# 06_LMS7002M_RF2.net
KiCad netlist of a schematic drawn in Altium Designer
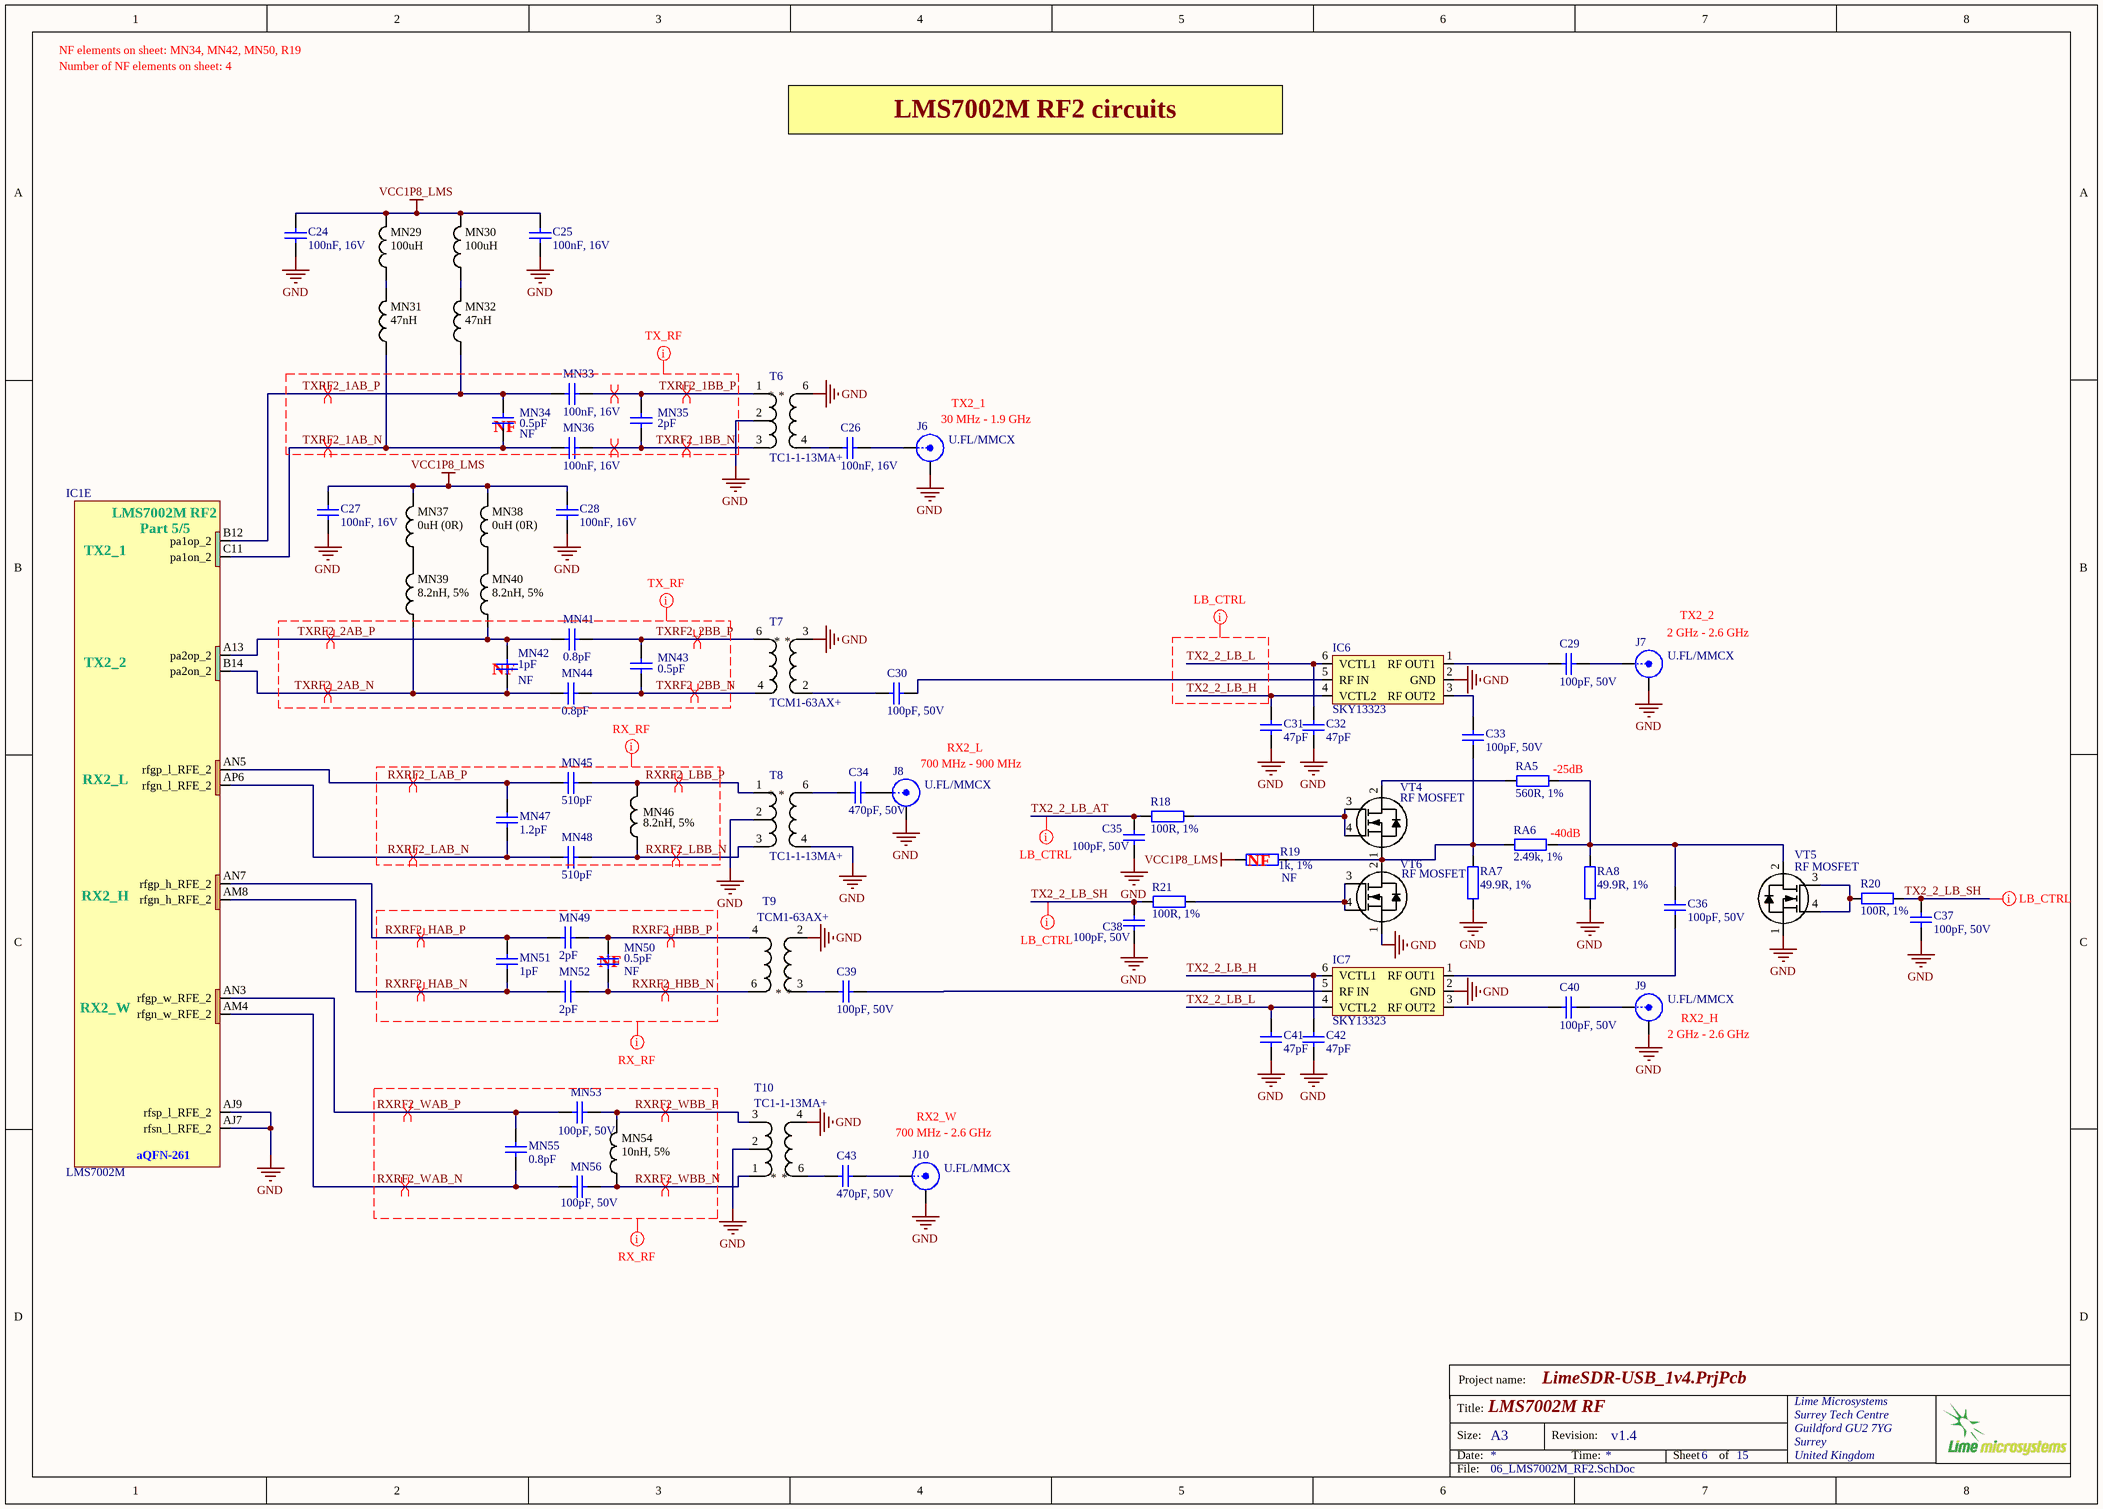
[diagram p0: 06_LMS7002M_RF2.SchDoc]

(export (version "E")
  (design (tool "Eeschema 10.0.6"))
  (components
    (comp (ref "C24")
      (value "100nF, 16V")
      (footprint "CAP0402")
      (fields
        (field (name "MANUFACTURER") "Murata Electronics")
        (field (name "TOLERANCE") "10 %")
        (field (name "MANUFACTURER PART NUMBER") "GRM155R71C104KA88D")
      )
      (libsource (lib "LimeMicroAltiumLib_schLib") (part "Cap_0402"))
    )
    (comp (ref "C25")
      (value "100nF, 16V")
      (footprint "CAP0402")
      (fields
        (field (name "MANUFACTURER") "Murata Electronics")
        (field (name "TOLERANCE") "10 %")
        (field (name "MANUFACTURER PART NUMBER") "GRM155R71C104KA88D")
      )
      (libsource (lib "LimeMicroAltiumLib_schLib") (part "Cap_0402"))
    )
    (comp (ref "C26")
      (value "100nF, 16V")
      (footprint "CAP0402")
      (fields
        (field (name "MANUFACTURER") "Murata Electronics")
        (field (name "TOLERANCE") "10 %")
        (field (name "MANUFACTURER PART NUMBER") "GRM155R71C104KA88D")
      )
      (libsource (lib "LimeMicroAltiumLib_schLib") (part "Cap_0402"))
    )
    (comp (ref "C27")
      (value "100nF, 16V")
      (footprint "CAP0402")
      (fields
        (field (name "MANUFACTURER") "Murata Electronics")
        (field (name "TOLERANCE") "10 %")
        (field (name "MANUFACTURER PART NUMBER") "GRM155R71C104KA88D")
      )
      (libsource (lib "LimeMicroAltiumLib_schLib") (part "Cap_0402"))
    )
    (comp (ref "C28")
      (value "100nF, 16V")
      (footprint "CAP0402")
      (fields
        (field (name "MANUFACTURER") "Murata Electronics")
        (field (name "TOLERANCE") "10 %")
        (field (name "MANUFACTURER PART NUMBER") "GRM155R71C104KA88D")
      )
      (libsource (lib "LimeMicroAltiumLib_schLib") (part "Cap_0402"))
    )
    (comp (ref "C29")
      (value "100pF, 50V")
      (footprint "CAP0402")
      (fields (field (name "TOLERANCE") "±5%") (field (name "MANUFACTURER") "Yageo"))
      (libsource (lib "LimeMicroAltiumLib_schLib") (part "Cap_0402"))
    )
    (comp (ref "C30")
      (value "100pF, 50V")
      (footprint "CAP0402")
      (fields (field (name "TOLERANCE") "±5%") (field (name "MANUFACTURER") "Yageo"))
      (libsource (lib "LimeMicroAltiumLib_schLib") (part "Cap_0402"))
    )
    (comp (ref "C31")
      (value "47pF")
      (footprint "CAP0402")
      (fields (field (name "TOLERANCE") "±1%") (field (name "MANUFACTURER") "TDK Corporation"))
      (libsource (lib "LimeMicroAltiumLib_schLib") (part "Cap_0402"))
    )
    (comp (ref "C32")
      (value "47pF")
      (footprint "CAP0402")
      (fields (field (name "TOLERANCE") "±1%") (field (name "MANUFACTURER") "TDK Corporation"))
      (libsource (lib "LimeMicroAltiumLib_schLib") (part "Cap_0402"))
    )
    (comp (ref "C33")
      (value "100pF, 50V")
      (footprint "CAP0402")
      (fields (field (name "TOLERANCE") "±5%") (field (name "MANUFACTURER") "Yageo"))
      (libsource (lib "LimeMicroAltiumLib_schLib") (part "Cap_0402"))
    )
    (comp (ref "C34")
      (value "470pF, 50V")
      (footprint "CAP0402")
      (fields
        (field (name "MANUFACTURER PART NUMBER") "C1005C0G1H471J050BA")
        (field (name "TOLERANCE") "±5%")
        (field (name "MANUFACTURER") "TDK Corporation")
      )
      (libsource (lib "LimeMicroAltiumLib_schLib") (part "Cap_0402"))
    )
    (comp (ref "C35")
      (value "100pF, 50V")
      (footprint "CAP0402")
      (fields (field (name "TOLERANCE") "±5%") (field (name "MANUFACTURER") "Yageo"))
      (libsource (lib "LimeMicroAltiumLib_schLib") (part "Cap_0402"))
    )
    (comp (ref "C36")
      (value "100pF, 50V")
      (footprint "CAP0402")
      (fields (field (name "TOLERANCE") "±5%") (field (name "MANUFACTURER") "Yageo"))
      (libsource (lib "LimeMicroAltiumLib_schLib") (part "Cap_0402"))
    )
    (comp (ref "C37")
      (value "100pF, 50V")
      (footprint "CAP0402")
      (fields (field (name "TOLERANCE") "±5%") (field (name "MANUFACTURER") "Yageo"))
      (libsource (lib "LimeMicroAltiumLib_schLib") (part "Cap_0402"))
    )
    (comp (ref "C38")
      (value "100pF, 50V")
      (footprint "CAP0402")
      (fields (field (name "TOLERANCE") "±5%") (field (name "MANUFACTURER") "Yageo"))
      (libsource (lib "LimeMicroAltiumLib_schLib") (part "Cap_0402"))
    )
    (comp (ref "C39")
      (value "100pF, 50V")
      (footprint "CAP0402")
      (fields (field (name "TOLERANCE") "±5%") (field (name "MANUFACTURER") "Yageo"))
      (libsource (lib "LimeMicroAltiumLib_schLib") (part "Cap_0402"))
    )
    (comp (ref "C40")
      (value "100pF, 50V")
      (footprint "CAP0402")
      (fields (field (name "TOLERANCE") "±5%") (field (name "MANUFACTURER") "Yageo"))
      (libsource (lib "LimeMicroAltiumLib_schLib") (part "Cap_0402"))
    )
    (comp (ref "C41")
      (value "47pF")
      (footprint "CAP0402")
      (fields (field (name "TOLERANCE") "±1%") (field (name "MANUFACTURER") "TDK Corporation"))
      (libsource (lib "LimeMicroAltiumLib_schLib") (part "Cap_0402"))
    )
    (comp (ref "C42")
      (value "47pF")
      (footprint "CAP0402")
      (fields (field (name "TOLERANCE") "±1%") (field (name "MANUFACTURER") "TDK Corporation"))
      (libsource (lib "LimeMicroAltiumLib_schLib") (part "Cap_0402"))
    )
    (comp (ref "C43")
      (value "470pF, 50V")
      (footprint "CAP0402")
      (fields
        (field (name "MANUFACTURER PART NUMBER") "C1005C0G1H471J050BA")
        (field (name "TOLERANCE") "±5%")
        (field (name "MANUFACTURER") "TDK Corporation")
      )
      (libsource (lib "LimeMicroAltiumLib_schLib") (part "Cap_0402"))
    )
    (comp (ref "IC1")
      (value "LMS7002M")
      (footprint "LMS7002M_v3")
      (fields (field (name "MANUFACTURER") "Lime Microsystems"))
      (libsource (lib "LimeMicroAltiumLib_schLib") (part "LMS7002M"))
    )
    (comp (ref "IC6")
      (value "SKY13323")
      (footprint "SKY13323-378LF")
      (description "SKY13323-378LF: 0.1-3.0 GHz GaAs SPDT Switch")
      (fields (field (name "MANUFACTURER") "Skyworks Solutions Inc."))
      (libsource (lib "LimeMicroAltiumLib_schLib") (part "SKY13323"))
    )
    (comp (ref "IC7")
      (value "SKY13323")
      (footprint "SKY13323-378LF")
      (description "SKY13323-378LF: 0.1-3.0 GHz GaAs SPDT Switch")
      (fields (field (name "MANUFACTURER") "Skyworks Solutions Inc."))
      (libsource (lib "LimeMicroAltiumLib_schLib") (part "SKY13323"))
    )
    (comp (ref "J6")
      (value "U.FL/MMCX")
      (footprint "MMCX_UFL_conn_u")
      (description "CONN UMC RCPT STR 50 OHM SMD")
      (fields (field (name "MANUFACTURER") "Molex, LLC"))
      (libsource (lib "LimeMicroAltiumLib_schLib") (part "RF_IF_connector"))
    )
    (comp (ref "J7")
      (value "U.FL/MMCX")
      (footprint "MMCX_UFL_conn_u")
      (description "CONN UMC RCPT STR 50 OHM SMD")
      (fields (field (name "MANUFACTURER") "Molex, LLC"))
      (libsource (lib "LimeMicroAltiumLib_schLib") (part "RF_IF_connector"))
    )
    (comp (ref "J8")
      (value "U.FL/MMCX")
      (footprint "MMCX_UFL_conn_u")
      (description "CONN UMC RCPT STR 50 OHM SMD")
      (fields (field (name "MANUFACTURER") "Molex, LLC"))
      (libsource (lib "LimeMicroAltiumLib_schLib") (part "RF_IF_connector"))
    )
    (comp (ref "J9")
      (value "U.FL/MMCX")
      (footprint "MMCX_UFL_conn_u")
      (description "CONN UMC RCPT STR 50 OHM SMD")
      (fields (field (name "MANUFACTURER") "Molex, LLC"))
      (libsource (lib "LimeMicroAltiumLib_schLib") (part "RF_IF_connector"))
    )
    (comp (ref "J10")
      (value "U.FL/MMCX")
      (footprint "MMCX_UFL_conn_u")
      (description "CONN UMC RCPT STR 50 OHM SMD")
      (fields (field (name "MANUFACTURER") "Molex, LLC"))
      (libsource (lib "LimeMicroAltiumLib_schLib") (part "RF_IF_connector"))
    )
    (comp (ref "MN29")
      (value "100uH")
      (footprint "RES0805")
      (fields
        (field (name "TOLERANCE") "±10%")
        (field (name "MANUFACTURER") "TDK Corporation")
        (field (name "MANUFACTURER PART NUMBER") "MLF2012C101KT000")
      )
      (libsource (lib "LimeMicroAltiumLib_schLib") (part "Inductor_0603"))
    )
    (comp (ref "MN30")
      (value "100uH")
      (footprint "RES0805")
      (fields
        (field (name "TOLERANCE") "±10%")
        (field (name "MANUFACTURER") "TDK Corporation")
        (field (name "MANUFACTURER PART NUMBER") "MLF2012C101KT000")
      )
      (libsource (lib "LimeMicroAltiumLib_schLib") (part "Inductor_0603"))
    )
    (comp (ref "MN31")
      (value "47nH")
      (footprint "RES0402")
      (fields
        (field (name "MANUFACTURER") "COILCRAFT")
        (field (name "MANUFACTURER PART NUMBER") "0402HP-47NXJLU")
      )
      (libsource (lib "LimeMicroAltiumLib_schLib") (part "Inductor_0603"))
    )
    (comp (ref "MN32")
      (value "47nH")
      (footprint "RES0402")
      (fields
        (field (name "MANUFACTURER") "COILCRAFT")
        (field (name "MANUFACTURER PART NUMBER") "0402HP-47NXJLU")
      )
      (libsource (lib "LimeMicroAltiumLib_schLib") (part "Inductor_0603"))
    )
    (comp (ref "MN33")
      (value "100nF, 16V")
      (footprint "CAP0402")
      (fields
        (field (name "MANUFACTURER") "Murata Electronics")
        (field (name "TOLERANCE") "10 %")
        (field (name "MANUFACTURER PART NUMBER") "GRM155R71C104KA88D")
      )
      (libsource (lib "LimeMicroAltiumLib_schLib") (part "Cap_0402"))
    )
    (comp (ref "MN34")
      (value "0.5pF")
      (footprint "CAP0402")
      (fields
        (field (name "ASSEMBLY INFO") "NF")
        (field (name "TOLERANCE") "±0.25pF")
        (field (name "MANUFACTURER") "Yageo")
      )
      (libsource (lib "LimeMicroAltiumLib_schLib") (part "Cap_0402"))
    )
    (comp (ref "MN35")
      (value "2pF")
      (footprint "CAP0402")
      (fields (field (name "MANUFACTURER PART NUMBER") "04025U2R0BAT2A") (field (name "MANUFACTURER") "AVX"))
      (libsource (lib "LimeMicroAltiumLib_schLib") (part "Cap_0402"))
    )
    (comp (ref "MN36")
      (value "100nF, 16V")
      (footprint "CAP0402")
      (fields
        (field (name "MANUFACTURER") "Murata Electronics")
        (field (name "TOLERANCE") "10 %")
        (field (name "MANUFACTURER PART NUMBER") "GRM155R71C104KA88D")
      )
      (libsource (lib "LimeMicroAltiumLib_schLib") (part "Cap_0402"))
    )
    (comp (ref "MN37")
      (value "0uH (0R)")
      (footprint "RES0805")
      (fields (field (name "MANUFACTURER") "BOURNS"))
      (libsource (lib "LimeMicroAltiumLib_schLib") (part "Inductor_0603"))
    )
    (comp (ref "MN38")
      (value "0uH (0R)")
      (footprint "RES0805")
      (fields (field (name "MANUFACTURER") "BOURNS"))
      (libsource (lib "LimeMicroAltiumLib_schLib") (part "Inductor_0603"))
    )
    (comp (ref "MN39")
      (value "8.2nH, 5%")
      (footprint "RES0402")
      (fields (field (name "MANUFACTURER") "COILCRAFT"))
      (libsource (lib "LimeMicroAltiumLib_schLib") (part "Inductor_0603"))
    )
    (comp (ref "MN40")
      (value "8.2nH, 5%")
      (footprint "RES0402")
      (fields (field (name "MANUFACTURER") "COILCRAFT"))
      (libsource (lib "LimeMicroAltiumLib_schLib") (part "Inductor_0603"))
    )
    (comp (ref "MN41")
      (value "0.8pF")
      (footprint "CAP0402")
      (fields
        (field (name "TOLERANCE") "±0.1pF")
        (field (name "MANUFACTURER") "Murata Electronics North America")
        (field (name "MANUFACTURER PART NUMBER") "GRM1555C1HR80BA01D")
      )
      (libsource (lib "LimeMicroAltiumLib_schLib") (part "Cap_0402"))
    )
    (comp (ref "MN42")
      (value "1pF")
      (footprint "CAP0402")
      (fields
        (field (name "ASSEMBLY INFO") "NF")
        (field (name "MANUFACTURER") "TDK Corporation")
        (field (name "TOLERANCE") "±0.1pF")
      )
      (libsource (lib "LimeMicroAltiumLib_schLib") (part "Cap_0402"))
    )
    (comp (ref "MN43")
      (value "0.5pF")
      (footprint "CAP0402")
      (fields (field (name "TOLERANCE") "±0.25pF") (field (name "MANUFACTURER") "Yageo"))
      (libsource (lib "LimeMicroAltiumLib_schLib") (part "Cap_0402"))
    )
    (comp (ref "MN44")
      (value "0.8pF")
      (footprint "CAP0402")
      (fields
        (field (name "TOLERANCE") "±0.1pF")
        (field (name "MANUFACTURER") "Murata Electronics North America")
        (field (name "MANUFACTURER PART NUMBER") "GRM1555C1HR80BA01D")
      )
      (libsource (lib "LimeMicroAltiumLib_schLib") (part "Cap_0402"))
    )
    (comp (ref "MN45")
      (value "510pF")
      (footprint "CAP0402")
      (fields
        (field (name "TOLERANCE") "±5%")
        (field (name "MANUFACTURER") "Murata Electronics North America")
        (field (name "MANUFACTURER PART NUMBER") "GRM1555C1H511JA01D")
      )
      (libsource (lib "LimeMicroAltiumLib_schLib") (part "Cap_0402"))
    )
    (comp (ref "MN46")
      (value "8.2nH, 5%")
      (footprint "RES0402")
      (fields (field (name "MANUFACTURER") "COILCRAFT"))
      (libsource (lib "LimeMicroAltiumLib_schLib") (part "Inductor_0603"))
    )
    (comp (ref "MN47")
      (value "1.2pF")
      (footprint "CAP0402")
      (fields
        (field (name "MANUFACTURER") "Murata Electronics North America")
        (field (name "MANUFACTURER PART NUMBER") "GRM1555C1H1R2CA01D")
        (field (name "TOLERANCE") "±0.25pF")
      )
      (libsource (lib "LimeMicroAltiumLib_schLib") (part "Cap_0402"))
    )
    (comp (ref "MN48")
      (value "510pF")
      (footprint "CAP0402")
      (fields
        (field (name "TOLERANCE") "±5%")
        (field (name "MANUFACTURER") "Murata Electronics North America")
        (field (name "MANUFACTURER PART NUMBER") "GRM1555C1H511JA01D")
      )
      (libsource (lib "LimeMicroAltiumLib_schLib") (part "Cap_0402"))
    )
    (comp (ref "MN49")
      (value "2pF")
      (footprint "CAP0402")
      (fields (field (name "MANUFACTURER PART NUMBER") "04025U2R0BAT2A") (field (name "MANUFACTURER") "AVX"))
      (libsource (lib "LimeMicroAltiumLib_schLib") (part "Cap_0402"))
    )
    (comp (ref "MN50")
      (value "0.5pF")
      (footprint "CAP0402")
      (fields
        (field (name "ASSEMBLY INFO") "NF")
        (field (name "TOLERANCE") "±0.25pF")
        (field (name "MANUFACTURER") "Yageo")
      )
      (libsource (lib "LimeMicroAltiumLib_schLib") (part "Cap_0402"))
    )
    (comp (ref "MN51")
      (value "1pF")
      (footprint "CAP0402")
      (fields (field (name "MANUFACTURER") "TDK Corporation") (field (name "TOLERANCE") "±0.1pF"))
      (libsource (lib "LimeMicroAltiumLib_schLib") (part "Cap_0402"))
    )
    (comp (ref "MN52")
      (value "2pF")
      (footprint "CAP0402")
      (fields (field (name "MANUFACTURER PART NUMBER") "04025U2R0BAT2A") (field (name "MANUFACTURER") "AVX"))
      (libsource (lib "LimeMicroAltiumLib_schLib") (part "Cap_0402"))
    )
    (comp (ref "MN53")
      (value "100pF, 50V")
      (footprint "CAP0402")
      (fields (field (name "TOLERANCE") "±5%") (field (name "MANUFACTURER") "Yageo"))
      (libsource (lib "LimeMicroAltiumLib_schLib") (part "Cap_0402"))
    )
    (comp (ref "MN54")
      (value "10nH, 5%")
      (footprint "RES0402")
      (fields (field (name "MANUFACTURER") "COILCRAFT"))
      (libsource (lib "LimeMicroAltiumLib_schLib") (part "Inductor_0603"))
    )
    (comp (ref "MN55")
      (value "0.8pF")
      (footprint "CAP0402")
      (fields
        (field (name "TOLERANCE") "±0.1pF")
        (field (name "MANUFACTURER") "Murata Electronics North America")
        (field (name "MANUFACTURER PART NUMBER") "GRM1555C1HR80BA01D")
      )
      (libsource (lib "LimeMicroAltiumLib_schLib") (part "Cap_0402"))
    )
    (comp (ref "MN56")
      (value "100pF, 50V")
      (footprint "CAP0402")
      (fields (field (name "TOLERANCE") "±5%") (field (name "MANUFACTURER") "Yageo"))
      (libsource (lib "LimeMicroAltiumLib_schLib") (part "Cap_0402"))
    )
    (comp (ref "R18")
      (value "100R, 1%")
      (footprint "RES0402")
      (fields (field (name "TOLERANCE") "±1%") (field (name "MANUFACTURER") "Stackpole Electronics Inc."))
      (libsource (lib "LimeFPGAboard_schLib") (part "Res_0402"))
    )
    (comp (ref "R19")
      (value "1k, 1%")
      (footprint "RES0402")
      (fields
        (field (name "ASSEMBLY INFO") "NF")
        (field (name "MANUFACTURER") "Stackpole Electronics Inc")
        (field (name "TOLERANCE") "±1%")
      )
      (libsource (lib "LimeMicroAltiumLib_schLib") (part "Res_0402"))
    )
    (comp (ref "R20")
      (value "100R, 1%")
      (footprint "RES0402")
      (fields (field (name "TOLERANCE") "±1%") (field (name "MANUFACTURER") "Stackpole Electronics Inc."))
      (libsource (lib "LimeFPGAboard_schLib") (part "Res_0402"))
    )
    (comp (ref "R21")
      (value "100R, 1%")
      (footprint "RES0402")
      (fields (field (name "TOLERANCE") "±1%") (field (name "MANUFACTURER") "Stackpole Electronics Inc."))
      (libsource (lib "LimeFPGAboard_schLib") (part "Res_0402"))
    )
    (comp (ref "RA5")
      (value "560R, 1%")
      (footprint "RES0402")
      (fields
        (field (name "MANUFACTURER PART NUMBER") "CRCW0402560RFKED")
        (field (name "TOLERANCE") "±1%")
        (field (name "MANUFACTURER") "Vishay Dale")
      )
      (libsource (lib "LimeMicroAltiumLib_schLib") (part "Res_0402"))
    )
    (comp (ref "RA6")
      (value "2.49k, 1%")
      (footprint "RES0402")
      (fields
        (field (name "TOLERANCE") "±1%")
        (field (name "MANUFACTURER PART NUMBER") "RC0402FR-072K49L")
        (field (name "MANUFACTURER") "Yageo")
      )
      (libsource (lib "LimeMicroAltiumLib_schLib") (part "Res_0402"))
    )
    (comp (ref "RA7")
      (value "49.9R, 1%")
      (footprint "RES0402")
      (fields
        (field (name "TOLERANCE") "±1%")
        (field (name "MANUFACTURER") "Samsung Electro-Mechanics America, Inc.")
        (field (name "MANUFACTURER PART NUMBER") "RC1005F49R9CS")
      )
      (libsource (lib "LimeMicroAltiumLib_schLib") (part "Res_0402"))
    )
    (comp (ref "RA8")
      (value "49.9R, 1%")
      (footprint "RES0402")
      (fields
        (field (name "TOLERANCE") "±1%")
        (field (name "MANUFACTURER") "Samsung Electro-Mechanics America, Inc.")
        (field (name "MANUFACTURER PART NUMBER") "RC1005F49R9CS")
      )
      (libsource (lib "LimeMicroAltiumLib_schLib") (part "Res_0402"))
    )
    (comp (ref "T6")
      (value "TC1-1-13MA+")
      (footprint "TC1-1-13MA+_v2")
      (fields (field (name "MANUFACTURER") "Mini-Circuits"))
      (libsource (lib "LimeMicroAltiumLib_schLib") (part "Balun"))
    )
    (comp (ref "T7")
      (value "TCM1-63AX+")
      (footprint "TCM1-63AX+_v2")
      (fields (field (name "MANUFACTURER") "Mini-circuits"))
      (libsource (lib "") (part "Balun_v2_1"))
    )
    (comp (ref "T8")
      (value "TC1-1-13MA+")
      (footprint "TC1-1-13MA+_v2")
      (fields (field (name "MANUFACTURER") "Mini-Circuits"))
      (libsource (lib "LimeMicroAltiumLib_schLib") (part "Balun"))
    )
    (comp (ref "T9")
      (value "TCM1-63AX+")
      (footprint "TCM1-63AX+_v2")
      (fields (field (name "MANUFACTURER") "Mini-circuits"))
      (libsource (lib "LimeMicroAltiumLib_schLib") (part "Balun_v2"))
    )
    (comp (ref "T10")
      (value "TC1-1-13MA+")
      (footprint "TC1-1-13MA+_v2")
      (fields (field (name "MANUFACTURER") "Mini-Circuits"))
      (libsource (lib "") (part "Balun_1"))
    )
    (comp (ref "VT4")
      (value "RF MOSFET")
      (footprint "BF1105R_SOT143R4")
      (fields (field (name "MANUFACTURER") "NXP Semiconductors"))
      (libsource (lib "LimeMicroAltiumLib_schLib") (part "BF1105R,215"))
    )
    (comp (ref "VT5")
      (value "RF MOSFET")
      (footprint "BF1105R_SOT143R4")
      (fields (field (name "MANUFACTURER") "NXP Semiconductors"))
      (libsource (lib "LimeMicroAltiumLib_schLib") (part "BF1105R,215"))
    )
    (comp (ref "VT6")
      (value "RF MOSFET")
      (footprint "BF1105R_SOT143R4")
      (fields (field (name "MANUFACTURER") "NXP Semiconductors"))
      (libsource (lib "LimeMicroAltiumLib_schLib") (part "BF1105R,215"))
    )
  )
  (nets
    (net (code "1") (name "/RXRF2_HAB_N") (class "Default")
      (node (ref "IC1") (pin "AM8") (pinfunction "rfgn_h_RFE_2_AM8") (pintype "passive"))
      (node (ref "MN51") (pin "1") (pinfunction "1_1") (pintype "passive"))
      (node (ref "MN52") (pin "2") (pinfunction "2_2") (pintype "passive"))
    )
    (net (code "2") (name "/RXRF2_HAB_P") (class "Default")
      (node (ref "IC1") (pin "AN7") (pinfunction "rfgp_h_RFE_2_AN7") (pintype "passive"))
      (node (ref "MN49") (pin "2") (pinfunction "2_2") (pintype "passive"))
      (node (ref "MN51") (pin "2") (pinfunction "2_2") (pintype "passive"))
    )
    (net (code "3") (name "/RXRF2_HBB_N") (class "Default")
      (node (ref "MN50") (pin "1") (pinfunction "1_1") (pintype "passive"))
      (node (ref "MN52") (pin "1") (pinfunction "1_1") (pintype "passive"))
      (node (ref "T9") (pin "6") (pinfunction "6_6") (pintype "passive"))
    )
    (net (code "4") (name "/RXRF2_HBB_P") (class "Default")
      (node (ref "MN49") (pin "1") (pinfunction "1_1") (pintype "passive"))
      (node (ref "MN50") (pin "2") (pinfunction "2_2") (pintype "passive"))
      (node (ref "T9") (pin "4") (pinfunction "4_4") (pintype "passive"))
    )
    (net (code "5") (name "/RXRF2_LAB_N") (class "Default")
      (node (ref "IC1") (pin "AP6") (pinfunction "rfgn_l_RFE_2_AP6") (pintype "passive"))
      (node (ref "MN47") (pin "1") (pinfunction "1_1") (pintype "passive"))
      (node (ref "MN48") (pin "2") (pinfunction "2_2") (pintype "passive"))
    )
    (net (code "6") (name "/RXRF2_LAB_P") (class "Default")
      (node (ref "IC1") (pin "AN5") (pinfunction "rfgp_l_RFE_2_AN5") (pintype "passive"))
      (node (ref "MN45") (pin "2") (pinfunction "2_2") (pintype "passive"))
      (node (ref "MN47") (pin "2") (pinfunction "2_2") (pintype "passive"))
    )
    (net (code "7") (name "/RXRF2_LBB_N") (class "Default")
      (node (ref "MN46") (pin "1") (pinfunction "1_1") (pintype "passive"))
      (node (ref "MN48") (pin "1") (pinfunction "1_1") (pintype "passive"))
      (node (ref "T8") (pin "3") (pinfunction "3_3") (pintype "passive"))
    )
    (net (code "8") (name "/RXRF2_LBB_P") (class "Default")
      (node (ref "MN45") (pin "1") (pinfunction "1_1") (pintype "passive"))
      (node (ref "MN46") (pin "2") (pinfunction "2_2") (pintype "passive"))
      (node (ref "T8") (pin "1") (pinfunction "1_1") (pintype "passive"))
    )
    (net (code "9") (name "/RXRF2_WAB_N") (class "Default")
      (node (ref "IC1") (pin "AM4") (pinfunction "rfgn_w_RFE_2_AM4") (pintype "passive"))
      (node (ref "MN55") (pin "2") (pinfunction "2_2") (pintype "passive"))
      (node (ref "MN56") (pin "2") (pinfunction "2_2") (pintype "passive"))
    )
    (net (code "10") (name "/RXRF2_WAB_P") (class "Default")
      (node (ref "IC1") (pin "AN3") (pinfunction "rfgp_w_RFE_2_AN3") (pintype "passive"))
      (node (ref "MN53") (pin "2") (pinfunction "2_2") (pintype "passive"))
      (node (ref "MN55") (pin "1") (pinfunction "1_1") (pintype "passive"))
    )
    (net (code "11") (name "/RXRF2_WBB_N") (class "Default")
      (node (ref "MN54") (pin "1") (pinfunction "1_1") (pintype "passive"))
      (node (ref "MN56") (pin "1") (pinfunction "1_1") (pintype "passive"))
      (node (ref "T10") (pin "1") (pinfunction "1_1") (pintype "passive"))
    )
    (net (code "12") (name "/RXRF2_WBB_P") (class "Default")
      (node (ref "MN53") (pin "1") (pinfunction "1_1") (pintype "passive"))
      (node (ref "MN54") (pin "2") (pinfunction "2_2") (pintype "passive"))
      (node (ref "T10") (pin "3") (pinfunction "3_3") (pintype "passive"))
    )
    (net (code "13") (name "/TX2_2_LB_AT") (class "Default")
      (node (ref "C35") (pin "1") (pinfunction "1_1") (pintype "passive"))
      (node (ref "R18") (pin "2") (pinfunction "2_2") (pintype "passive"))
    )
    (net (code "14") (name "/TX2_2_LB_H") (class "Default")
      (node (ref "C31") (pin "2") (pinfunction "2_2") (pintype "passive"))
      (node (ref "C42") (pin "2") (pinfunction "2_2") (pintype "passive"))
      (node (ref "IC6") (pin "4") (pinfunction "VCTL2_4") (pintype "input"))
      (node (ref "IC7") (pin "6") (pinfunction "VCTL1_6") (pintype "input"))
    )
    (net (code "15") (name "/TX2_2_LB_L") (class "Default")
      (node (ref "C32") (pin "2") (pinfunction "2_2") (pintype "passive"))
      (node (ref "C41") (pin "2") (pinfunction "2_2") (pintype "passive"))
      (node (ref "IC6") (pin "6") (pinfunction "VCTL1_6") (pintype "input"))
      (node (ref "IC7") (pin "4") (pinfunction "VCTL2_4") (pintype "input"))
    )
    (net (code "16") (name "/TX2_2_LB_SH") (class "Default")
      (node (ref "C37") (pin "1") (pinfunction "1_1") (pintype "passive"))
      (node (ref "C38") (pin "1") (pinfunction "1_1") (pintype "passive"))
      (node (ref "R20") (pin "1") (pinfunction "1_1") (pintype "passive"))
      (node (ref "R21") (pin "2") (pinfunction "2_2") (pintype "passive"))
    )
    (net (code "17") (name "/TXRF2_1AB_N") (class "Default")
      (node (ref "IC1") (pin "C11") (pinfunction "pa1on_2_C11") (pintype "passive"))
      (node (ref "MN31") (pin "1") (pinfunction "1_1") (pintype "passive"))
      (node (ref "MN34") (pin "1") (pinfunction "1_1") (pintype "passive"))
      (node (ref "MN36") (pin "1") (pinfunction "1_1") (pintype "passive"))
    )
    (net (code "18") (name "/TXRF2_1AB_P") (class "Default")
      (node (ref "IC1") (pin "B12") (pinfunction "pa1op_2_B12") (pintype "passive"))
      (node (ref "MN32") (pin "1") (pinfunction "1_1") (pintype "passive"))
      (node (ref "MN33") (pin "2") (pinfunction "2_2") (pintype "passive"))
      (node (ref "MN34") (pin "2") (pinfunction "2_2") (pintype "passive"))
    )
    (net (code "19") (name "/TXRF2_1BB_N") (class "Default")
      (node (ref "MN35") (pin "1") (pinfunction "1_1") (pintype "passive"))
      (node (ref "MN36") (pin "2") (pinfunction "2_2") (pintype "passive"))
      (node (ref "T6") (pin "3") (pinfunction "3_3") (pintype "passive"))
    )
    (net (code "20") (name "/TXRF2_1BB_P") (class "Default")
      (node (ref "MN33") (pin "1") (pinfunction "1_1") (pintype "passive"))
      (node (ref "MN35") (pin "2") (pinfunction "2_2") (pintype "passive"))
      (node (ref "T6") (pin "1") (pinfunction "1_1") (pintype "passive"))
    )
    (net (code "21") (name "/TXRF2_2AB_N") (class "Default")
      (node (ref "IC1") (pin "B14") (pinfunction "pa2on_2_B14") (pintype "passive"))
      (node (ref "MN39") (pin "1") (pinfunction "1_1") (pintype "passive"))
      (node (ref "MN42") (pin "2") (pinfunction "2_2") (pintype "passive"))
      (node (ref "MN44") (pin "2") (pinfunction "2_2") (pintype "passive"))
    )
    (net (code "22") (name "/TXRF2_2AB_P") (class "Default")
      (node (ref "IC1") (pin "A13") (pinfunction "pa2op_2_A13") (pintype "passive"))
      (node (ref "MN40") (pin "1") (pinfunction "1_1") (pintype "passive"))
      (node (ref "MN41") (pin "2") (pinfunction "2_2") (pintype "passive"))
      (node (ref "MN42") (pin "1") (pinfunction "1_1") (pintype "passive"))
    )
    (net (code "23") (name "/TXRF2_2BB_N") (class "Default")
      (node (ref "MN43") (pin "1") (pinfunction "1_1") (pintype "passive"))
      (node (ref "MN44") (pin "1") (pinfunction "1_1") (pintype "passive"))
      (node (ref "T7") (pin "4") (pinfunction "4_4") (pintype "passive"))
    )
    (net (code "24") (name "/TXRF2_2BB_P") (class "Default")
      (node (ref "MN41") (pin "1") (pinfunction "1_1") (pintype "passive"))
      (node (ref "MN43") (pin "2") (pinfunction "2_2") (pintype "passive"))
      (node (ref "T7") (pin "6") (pinfunction "6_6") (pintype "passive"))
    )
    (net (code "25") (name "GND") (class "Default")
      (node (ref "C24") (pin "1") (pinfunction "1_1") (pintype "passive"))
      (node (ref "C25") (pin "1") (pinfunction "1_1") (pintype "passive"))
      (node (ref "C27") (pin "1") (pinfunction "1_1") (pintype "passive"))
      (node (ref "C28") (pin "1") (pinfunction "1_1") (pintype "passive"))
      (node (ref "C31") (pin "1") (pinfunction "1_1") (pintype "passive"))
      (node (ref "C32") (pin "1") (pinfunction "1_1") (pintype "passive"))
      (node (ref "C35") (pin "2") (pinfunction "2_2") (pintype "passive"))
      (node (ref "C37") (pin "2") (pinfunction "2_2") (pintype "passive"))
      (node (ref "C38") (pin "2") (pinfunction "2_2") (pintype "passive"))
      (node (ref "C41") (pin "1") (pinfunction "1_1") (pintype "passive"))
      (node (ref "C42") (pin "1") (pinfunction "1_1") (pintype "passive"))
      (node (ref "IC1") (pin "AJ7") (pinfunction "rfsn_l_RFE_2_AJ7") (pintype "passive"))
      (node (ref "IC1") (pin "AJ9") (pinfunction "rfsp_l_RFE_2_AJ9") (pintype "passive"))
      (node (ref "IC6") (pin "2") (pinfunction "GND_2") (pintype "passive"))
      (node (ref "IC7") (pin "2") (pinfunction "GND_2") (pintype "passive"))
      (node (ref "J10") (pin "2") (pinfunction "Y_2") (pintype "passive"))
      (node (ref "J6") (pin "2") (pinfunction "Y_2") (pintype "passive"))
      (node (ref "J7") (pin "2") (pinfunction "Y_2") (pintype "passive"))
      (node (ref "J8") (pin "2") (pinfunction "Y_2") (pintype "passive"))
      (node (ref "J9") (pin "2") (pinfunction "Y_2") (pintype "passive"))
      (node (ref "RA7") (pin "1") (pinfunction "1_1") (pintype "passive"))
      (node (ref "RA8") (pin "1") (pinfunction "1_1") (pintype "passive"))
      (node (ref "T10") (pin "2") (pinfunction "2_2") (pintype "passive"))
      (node (ref "T10") (pin "4") (pinfunction "4_4") (pintype "passive"))
      (node (ref "T6") (pin "2") (pinfunction "2_2") (pintype "passive"))
      (node (ref "T6") (pin "6") (pinfunction "6_6") (pintype "passive"))
      (node (ref "T7") (pin "3") (pinfunction "3_3") (pintype "passive"))
      (node (ref "T8") (pin "2") (pinfunction "2_2") (pintype "passive"))
      (node (ref "T8") (pin "4") (pinfunction "4_4") (pintype "passive"))
      (node (ref "T9") (pin "2") (pinfunction "2_2") (pintype "passive"))
      (node (ref "VT5") (pin "1") (pinfunction "S_1") (pintype "passive"))
      (node (ref "VT6") (pin "1") (pinfunction "S_1") (pintype "passive"))
    )
    (net (code "26") (name "Net-(C26-Pad2)") (class "Default")
      (node (ref "C26") (pin "2") (pinfunction "2_2") (pintype "passive"))
      (node (ref "T6") (pin "4") (pinfunction "4_4") (pintype "passive"))
    )
    (net (code "27") (name "Net-(C30-Pad2)") (class "Default")
      (node (ref "C30") (pin "2") (pinfunction "2_2") (pintype "passive"))
      (node (ref "T7") (pin "2") (pinfunction "2_2") (pintype "passive"))
    )
    (net (code "28") (name "Net-(C34-Pad2)") (class "Default")
      (node (ref "C34") (pin "2") (pinfunction "2_2") (pintype "passive"))
      (node (ref "T8") (pin "6") (pinfunction "6_6") (pintype "passive"))
    )
    (net (code "29") (name "Net-(C39-Pad2)") (class "Default")
      (node (ref "C39") (pin "2") (pinfunction "2_2") (pintype "passive"))
      (node (ref "T9") (pin "3") (pinfunction "3_3") (pintype "passive"))
    )
    (net (code "30") (name "Net-(C43-Pad2)") (class "Default")
      (node (ref "C43") (pin "2") (pinfunction "2_2") (pintype "passive"))
      (node (ref "T10") (pin "6") (pinfunction "6_6") (pintype "passive"))
    )
    (net (code "31") (name "Net-(IC6-RF_IN)") (class "Default")
      (node (ref "C30") (pin "1") (pinfunction "1_1") (pintype "passive"))
      (node (ref "IC6") (pin "5") (pinfunction "RF_IN_5") (pintype "input"))
    )
    (net (code "32") (name "Net-(IC6-RF_OUT1)") (class "Default")
      (node (ref "C29") (pin "2") (pinfunction "2_2") (pintype "passive"))
      (node (ref "IC6") (pin "1") (pinfunction "RF_OUT1_1") (pintype "output"))
    )
    (net (code "33") (name "Net-(IC6-RF_OUT2)") (class "Default")
      (node (ref "C33") (pin "1") (pinfunction "1_1") (pintype "passive"))
      (node (ref "IC6") (pin "3") (pinfunction "RF_OUT2_3") (pintype "output"))
    )
    (net (code "34") (name "Net-(IC7-RF_IN)") (class "Default")
      (node (ref "C39") (pin "1") (pinfunction "1_1") (pintype "passive"))
      (node (ref "IC7") (pin "5") (pinfunction "RF_IN_5") (pintype "input"))
    )
    (net (code "35") (name "Net-(IC7-RF_OUT1)") (class "Default")
      (node (ref "C36") (pin "2") (pinfunction "2_2") (pintype "passive"))
      (node (ref "IC7") (pin "1") (pinfunction "RF_OUT1_1") (pintype "output"))
    )
    (net (code "36") (name "Net-(IC7-RF_OUT2)") (class "Default")
      (node (ref "C40") (pin "2") (pinfunction "2_2") (pintype "passive"))
      (node (ref "IC7") (pin "3") (pinfunction "RF_OUT2_3") (pintype "output"))
    )
    (net (code "37") (name "Net-(J6-X)") (class "Default")
      (node (ref "C26") (pin "1") (pinfunction "1_1") (pintype "passive"))
      (node (ref "J6") (pin "1") (pinfunction "X_1") (pintype "passive"))
    )
    (net (code "38") (name "Net-(J7-X)") (class "Default")
      (node (ref "C29") (pin "1") (pinfunction "1_1") (pintype "passive"))
      (node (ref "J7") (pin "1") (pinfunction "X_1") (pintype "passive"))
    )
    (net (code "39") (name "Net-(J8-X)") (class "Default")
      (node (ref "C34") (pin "1") (pinfunction "1_1") (pintype "passive"))
      (node (ref "J8") (pin "1") (pinfunction "X_1") (pintype "passive"))
    )
    (net (code "40") (name "Net-(J9-X)") (class "Default")
      (node (ref "C40") (pin "1") (pinfunction "1_1") (pintype "passive"))
      (node (ref "J9") (pin "1") (pinfunction "X_1") (pintype "passive"))
    )
    (net (code "41") (name "Net-(J10-X)") (class "Default")
      (node (ref "C43") (pin "1") (pinfunction "1_1") (pintype "passive"))
      (node (ref "J10") (pin "1") (pinfunction "X_1") (pintype "passive"))
    )
    (net (code "42") (name "Net-(MN29-Pad1)") (class "Default")
      (node (ref "MN29") (pin "1") (pinfunction "1_1") (pintype "passive"))
      (node (ref "MN31") (pin "2") (pinfunction "2_2") (pintype "passive"))
    )
    (net (code "43") (name "Net-(MN30-Pad1)") (class "Default")
      (node (ref "MN30") (pin "1") (pinfunction "1_1") (pintype "passive"))
      (node (ref "MN32") (pin "2") (pinfunction "2_2") (pintype "passive"))
    )
    (net (code "44") (name "Net-(MN37-Pad1)") (class "Default")
      (node (ref "MN37") (pin "1") (pinfunction "1_1") (pintype "passive"))
      (node (ref "MN39") (pin "2") (pinfunction "2_2") (pintype "passive"))
    )
    (net (code "45") (name "Net-(MN38-Pad1)") (class "Default")
      (node (ref "MN38") (pin "1") (pinfunction "1_1") (pintype "passive"))
      (node (ref "MN40") (pin "2") (pinfunction "2_2") (pintype "passive"))
    )
    (net (code "46") (name "Net-(VT4-D)") (class "Default")
      (node (ref "RA5") (pin "2") (pinfunction "2_2") (pintype "passive"))
      (node (ref "VT4") (pin "2") (pinfunction "D_2") (pintype "passive"))
    )
    (net (code "47") (name "Net-(VT4-G1)") (class "Default")
      (node (ref "R18") (pin "1") (pinfunction "1_1") (pintype "passive"))
      (node (ref "VT4") (pin "3") (pinfunction "G2_3") (pintype "passive"))
      (node (ref "VT4") (pin "4") (pinfunction "G1_4") (pintype "passive"))
    )
    (net (code "48") (name "Net-(VT4-S)") (class "Default")
      (node (ref "C33") (pin "2") (pinfunction "2_2") (pintype "passive"))
      (node (ref "R19") (pin "1") (pinfunction "1_1") (pintype "passive"))
      (node (ref "RA6") (pin "1") (pinfunction "1_1") (pintype "passive"))
      (node (ref "RA7") (pin "2") (pinfunction "2_2") (pintype "passive"))
      (node (ref "VT4") (pin "1") (pinfunction "S_1") (pintype "passive"))
      (node (ref "VT6") (pin "2") (pinfunction "D_2") (pintype "passive"))
    )
    (net (code "49") (name "Net-(VT5-D)") (class "Default")
      (node (ref "C36") (pin "1") (pinfunction "1_1") (pintype "passive"))
      (node (ref "RA5") (pin "1") (pinfunction "1_1") (pintype "passive"))
      (node (ref "RA6") (pin "2") (pinfunction "2_2") (pintype "passive"))
      (node (ref "RA8") (pin "2") (pinfunction "2_2") (pintype "passive"))
      (node (ref "VT5") (pin "2") (pinfunction "D_2") (pintype "passive"))
    )
    (net (code "50") (name "Net-(VT5-G1)") (class "Default")
      (node (ref "R20") (pin "2") (pinfunction "2_2") (pintype "passive"))
      (node (ref "VT5") (pin "3") (pinfunction "G2_3") (pintype "passive"))
      (node (ref "VT5") (pin "4") (pinfunction "G1_4") (pintype "passive"))
    )
    (net (code "51") (name "Net-(VT6-G1)") (class "Default")
      (node (ref "R21") (pin "1") (pinfunction "1_1") (pintype "passive"))
      (node (ref "VT6") (pin "3") (pinfunction "G2_3") (pintype "passive"))
      (node (ref "VT6") (pin "4") (pinfunction "G1_4") (pintype "passive"))
    )
    (net (code "52") (name "VCC1P8_LMS") (class "Default")
      (node (ref "C24") (pin "2") (pinfunction "2_2") (pintype "passive"))
      (node (ref "C25") (pin "2") (pinfunction "2_2") (pintype "passive"))
      (node (ref "C27") (pin "2") (pinfunction "2_2") (pintype "passive"))
      (node (ref "C28") (pin "2") (pinfunction "2_2") (pintype "passive"))
      (node (ref "MN29") (pin "2") (pinfunction "2_2") (pintype "passive"))
      (node (ref "MN30") (pin "2") (pinfunction "2_2") (pintype "passive"))
      (node (ref "MN37") (pin "2") (pinfunction "2_2") (pintype "passive"))
      (node (ref "MN38") (pin "2") (pinfunction "2_2") (pintype "passive"))
      (node (ref "R19") (pin "2") (pinfunction "2_2") (pintype "passive"))
    )
  )
)
